# core.net
KiCad netlist of a schematic drawn in Altium Designer
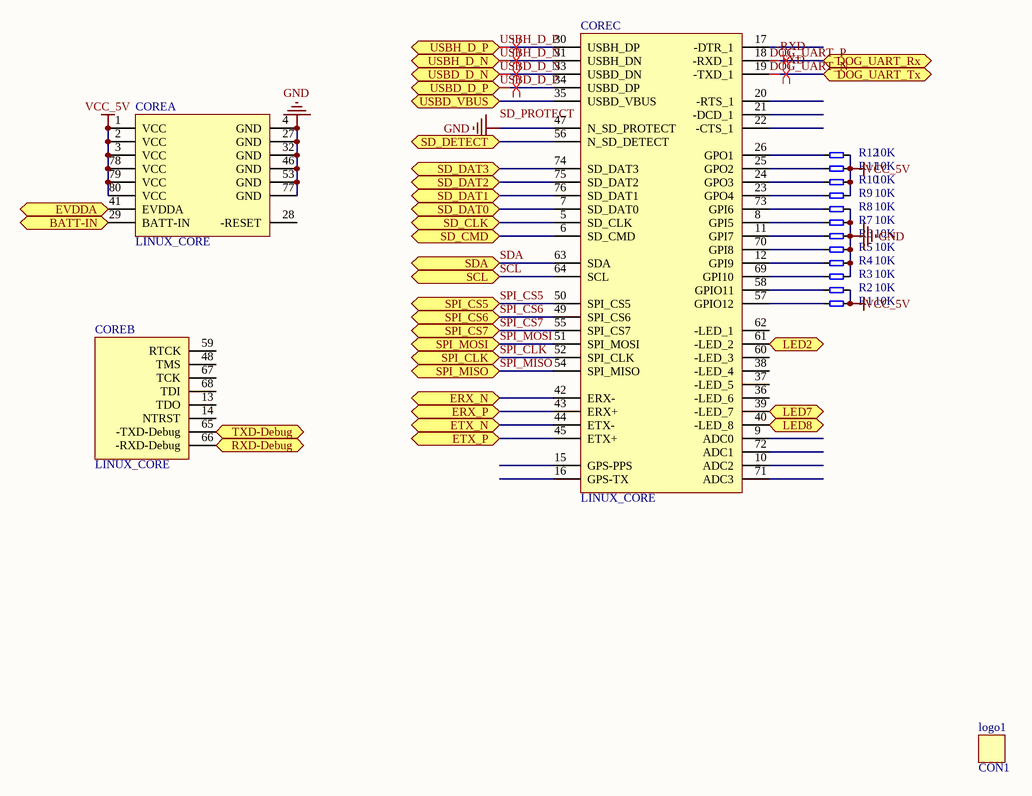
[diagram p0: core.SchDoc]

(export (version "E")
  (design (tool "Eeschema 10.0.6"))
  (components
    (comp (ref "CORE")
      (value "LINUX_CORE")
      (footprint "LINUX_CORE")
      (libsource (lib "Schlib1") (part "LINUX_CORE"))
    )
    (comp (ref "logo1")
      (value "CON1")
      (footprint "logo")
      (description "Connector")
      (libsource (lib "接插件") (part "CON1"))
    )
    (comp (ref "R1")
      (value "10K")
      (footprint "0805/2012 R3")
      (description "Resistor")
      (libsource (lib "标准元件库") (part "RES2"))
    )
    (comp (ref "R2")
      (value "10K")
      (footprint "0805/2012 R3")
      (description "Resistor")
      (libsource (lib "标准元件库") (part "RES2"))
    )
    (comp (ref "R3")
      (value "10K")
      (footprint "0805/2012 R3")
      (description "Resistor")
      (libsource (lib "标准元件库") (part "RES2"))
    )
    (comp (ref "R4")
      (value "10K")
      (footprint "0805/2012 R3")
      (description "Resistor")
      (libsource (lib "标准元件库") (part "RES2"))
    )
    (comp (ref "R5")
      (value "10K")
      (footprint "0805/2012 R3")
      (description "Resistor")
      (libsource (lib "标准元件库") (part "RES2"))
    )
    (comp (ref "R6")
      (value "10K")
      (footprint "0805/2012 R3")
      (description "Resistor")
      (libsource (lib "标准元件库") (part "RES2"))
    )
    (comp (ref "R7")
      (value "10K")
      (footprint "0805/2012 R3")
      (description "Resistor")
      (libsource (lib "标准元件库") (part "RES2"))
    )
    (comp (ref "R8")
      (value "10K")
      (footprint "0805/2012 R3")
      (description "Resistor")
      (libsource (lib "标准元件库") (part "RES2"))
    )
    (comp (ref "R9")
      (value "10K")
      (footprint "0805/2012 R3")
      (description "Resistor")
      (libsource (lib "标准元件库") (part "RES2"))
    )
    (comp (ref "R10")
      (value "10K")
      (footprint "0805/2012 R3")
      (description "Resistor")
      (libsource (lib "标准元件库") (part "RES2"))
    )
    (comp (ref "R11")
      (value "10K")
      (footprint "0805/2012 R3")
      (description "Resistor")
      (libsource (lib "标准元件库") (part "RES2"))
    )
    (comp (ref "R12")
      (value "10K")
      (footprint "0805/2012 R3")
      (description "Resistor")
      (libsource (lib "标准元件库") (part "RES2"))
    )
  )
  (nets
    (net (code "3") (name "/BATT-IN") (class "Default")
      (node (ref "CORE") (pin "29") (pinfunction "BATT-IN_29") (pintype "passive"))
    )
    (net (code "4") (name "/DOG_UART_N") (class "Default")
      (node (ref "CORE") (pin "19") (pinfunction "-TXD_1_19") (pintype "passive"))
    )
    (net (code "5") (name "/DOG_UART_P") (class "Default")
      (node (ref "CORE") (pin "18") (pinfunction "-RXD_1_18") (pintype "passive"))
    )
    (net (code "6") (name "/ERX_N") (class "Default")
      (node (ref "CORE") (pin "42") (pinfunction "ERX-_42") (pintype "passive"))
    )
    (net (code "7") (name "/ERX_P") (class "Default")
      (node (ref "CORE") (pin "43") (pinfunction "ERX+_43") (pintype "passive"))
    )
    (net (code "8") (name "/ETX_N") (class "Default")
      (node (ref "CORE") (pin "44") (pinfunction "ETX-_44") (pintype "passive"))
    )
    (net (code "9") (name "/ETX_P") (class "Default")
      (node (ref "CORE") (pin "45") (pinfunction "ETX+_45") (pintype "passive"))
    )
    (net (code "10") (name "/EVDDA") (class "Default")
      (node (ref "CORE") (pin "41") (pinfunction "EVDDA_41") (pintype "passive"))
    )
    (net (code "11") (name "/LED2") (class "Default")
      (node (ref "CORE") (pin "61") (pinfunction "-LED_2_61") (pintype "passive"))
    )
    (net (code "12") (name "/LED7") (class "Default")
      (node (ref "CORE") (pin "39") (pinfunction "-LED_7_39") (pintype "passive"))
    )
    (net (code "13") (name "/LED8") (class "Default")
      (node (ref "CORE") (pin "40") (pinfunction "-LED_8_40") (pintype "passive"))
    )
    (net (code "14") (name "/RXD-Debug") (class "Default")
      (node (ref "CORE") (pin "66") (pinfunction "-RXD-Debug_66") (pintype "passive"))
    )
    (net (code "15") (name "/SCL") (class "Default")
      (node (ref "CORE") (pin "64") (pinfunction "SCL_64") (pintype "passive"))
    )
    (net (code "16") (name "/SDA") (class "Default")
      (node (ref "CORE") (pin "63") (pinfunction "SDA_63") (pintype "passive"))
    )
    (net (code "17") (name "/SD_CLK") (class "Default")
      (node (ref "CORE") (pin "5") (pinfunction "SD_CLK_5") (pintype "passive"))
    )
    (net (code "18") (name "/SD_CMD") (class "Default")
      (node (ref "CORE") (pin "6") (pinfunction "SD_CMD_6") (pintype "passive"))
    )
    (net (code "19") (name "/SD_DAT0") (class "Default")
      (node (ref "CORE") (pin "7") (pinfunction "SD_DAT0_7") (pintype "passive"))
    )
    (net (code "20") (name "/SD_DAT1") (class "Default")
      (node (ref "CORE") (pin "76") (pinfunction "SD_DAT1_76") (pintype "passive"))
    )
    (net (code "21") (name "/SD_DAT2") (class "Default")
      (node (ref "CORE") (pin "75") (pinfunction "SD_DAT2_75") (pintype "passive"))
    )
    (net (code "22") (name "/SD_DAT3") (class "Default")
      (node (ref "CORE") (pin "74") (pinfunction "SD_DAT3_74") (pintype "passive"))
    )
    (net (code "23") (name "/SD_DETECT") (class "Default")
      (node (ref "CORE") (pin "56") (pinfunction "N_SD_DETECT_56") (pintype "passive"))
    )
    (net (code "25") (name "/SPI_CLK") (class "Default")
      (node (ref "CORE") (pin "52") (pinfunction "SPI_CLK_52") (pintype "passive"))
    )
    (net (code "26") (name "/SPI_CS5") (class "Default")
      (node (ref "CORE") (pin "50") (pinfunction "SPI_CS5_50") (pintype "passive"))
    )
    (net (code "27") (name "/SPI_CS6") (class "Default")
      (node (ref "CORE") (pin "49") (pinfunction "SPI_CS6_49") (pintype "passive"))
    )
    (net (code "28") (name "/SPI_CS7") (class "Default")
      (node (ref "CORE") (pin "55") (pinfunction "SPI_CS7_55") (pintype "passive"))
    )
    (net (code "29") (name "/SPI_MISO") (class "Default")
      (node (ref "CORE") (pin "54") (pinfunction "SPI_MISO_54") (pintype "passive"))
    )
    (net (code "30") (name "/SPI_MOSI") (class "Default")
      (node (ref "CORE") (pin "51") (pinfunction "SPI_MOSI_51") (pintype "passive"))
    )
    (net (code "31") (name "/TXD-Debug") (class "Default")
      (node (ref "CORE") (pin "65") (pinfunction "-TXD-Debug_65") (pintype "passive"))
    )
    (net (code "32") (name "/USBD_D_N") (class "Default")
      (node (ref "CORE") (pin "33") (pinfunction "USBD_DN_33") (pintype "passive"))
    )
    (net (code "33") (name "/USBD_D_P") (class "Default")
      (node (ref "CORE") (pin "34") (pinfunction "USBD_DP_34") (pintype "passive"))
    )
    (net (code "34") (name "/USBD_VBUS") (class "Default")
      (node (ref "CORE") (pin "35") (pinfunction "USBD_VBUS_35") (pintype "passive"))
    )
    (net (code "35") (name "/USBH_D_N") (class "Default")
      (node (ref "CORE") (pin "31") (pinfunction "USBH_DN_31") (pintype "passive"))
    )
    (net (code "36") (name "/USBH_D_P") (class "Default")
      (node (ref "CORE") (pin "30") (pinfunction "USBH_DP_30") (pintype "passive"))
    )
    (net (code "37") (name "GND") (class "Default")
      (node (ref "CORE") (pin "27") (pinfunction "GND_27") (pintype "passive"))
      (node (ref "CORE") (pin "32") (pinfunction "GND_32") (pintype "passive"))
      (node (ref "CORE") (pin "4") (pinfunction "GND_4") (pintype "passive"))
      (node (ref "CORE") (pin "46") (pinfunction "GND_46") (pintype "passive"))
      (node (ref "CORE") (pin "47") (pinfunction "N_SD_PROTECT_47") (pintype "passive"))
      (node (ref "CORE") (pin "53") (pinfunction "GND_53") (pintype "passive"))
      (node (ref "CORE") (pin "77") (pinfunction "GND_77") (pintype "passive"))
      (node (ref "R3") (pin "2") (pinfunction "2_2") (pintype "passive"))
      (node (ref "R4") (pin "2") (pinfunction "2_2") (pintype "passive"))
      (node (ref "R5") (pin "2") (pinfunction "2_2") (pintype "passive"))
      (node (ref "R6") (pin "2") (pinfunction "2_2") (pintype "passive"))
      (node (ref "R7") (pin "2") (pinfunction "2_2") (pintype "passive"))
      (node (ref "R8") (pin "2") (pinfunction "2_2") (pintype "passive"))
    )
    (net (code "38") (name "Net-(COREC-GPI5)") (class "Default")
      (node (ref "CORE") (pin "8") (pinfunction "GPI5_8") (pintype "passive"))
      (node (ref "R7") (pin "1") (pinfunction "1_1") (pintype "passive"))
    )
    (net (code "39") (name "Net-(COREC-GPI6)") (class "Default")
      (node (ref "CORE") (pin "73") (pinfunction "GPI6_73") (pintype "passive"))
      (node (ref "R8") (pin "1") (pinfunction "1_1") (pintype "passive"))
    )
    (net (code "40") (name "Net-(COREC-GPI7)") (class "Default")
      (node (ref "CORE") (pin "11") (pinfunction "GPI7_11") (pintype "passive"))
      (node (ref "R6") (pin "1") (pinfunction "1_1") (pintype "passive"))
    )
    (net (code "41") (name "Net-(COREC-GPI8)") (class "Default")
      (node (ref "CORE") (pin "70") (pinfunction "GPI8_70") (pintype "passive"))
      (node (ref "R5") (pin "1") (pinfunction "1_1") (pintype "passive"))
    )
    (net (code "42") (name "Net-(COREC-GPI9)") (class "Default")
      (node (ref "CORE") (pin "12") (pinfunction "GPI9_12") (pintype "passive"))
      (node (ref "R4") (pin "1") (pinfunction "1_1") (pintype "passive"))
    )
    (net (code "43") (name "Net-(COREC-GPI10)") (class "Default")
      (node (ref "CORE") (pin "69") (pinfunction "GPI10_69") (pintype "passive"))
      (node (ref "R3") (pin "1") (pinfunction "1_1") (pintype "passive"))
    )
    (net (code "44") (name "Net-(COREC-GPIO11)") (class "Default")
      (node (ref "CORE") (pin "58") (pinfunction "GPIO11_58") (pintype "passive"))
      (node (ref "R2") (pin "1") (pinfunction "1_1") (pintype "passive"))
    )
    (net (code "45") (name "Net-(COREC-GPIO12)") (class "Default")
      (node (ref "CORE") (pin "57") (pinfunction "GPIO12_57") (pintype "passive"))
      (node (ref "R1") (pin "1") (pinfunction "1_1") (pintype "passive"))
    )
    (net (code "46") (name "Net-(COREC-GPO1)") (class "Default")
      (node (ref "CORE") (pin "26") (pinfunction "GPO1_26") (pintype "passive"))
      (node (ref "R12") (pin "1") (pinfunction "1_1") (pintype "passive"))
    )
    (net (code "47") (name "Net-(COREC-GPO2)") (class "Default")
      (node (ref "CORE") (pin "25") (pinfunction "GPO2_25") (pintype "passive"))
      (node (ref "R11") (pin "1") (pinfunction "1_1") (pintype "passive"))
    )
    (net (code "48") (name "Net-(COREC-GPO3)") (class "Default")
      (node (ref "CORE") (pin "24") (pinfunction "GPO3_24") (pintype "passive"))
      (node (ref "R10") (pin "1") (pinfunction "1_1") (pintype "passive"))
    )
    (net (code "49") (name "Net-(COREC-GPO4)") (class "Default")
      (node (ref "CORE") (pin "23") (pinfunction "GPO4_23") (pintype "passive"))
      (node (ref "R9") (pin "1") (pinfunction "1_1") (pintype "passive"))
    )
    (net (code "50") (name "VCC_5V") (class "Default")
      (node (ref "CORE") (pin "1") (pinfunction "VCC_1") (pintype "passive"))
      (node (ref "CORE") (pin "2") (pinfunction "VCC_2") (pintype "passive"))
      (node (ref "CORE") (pin "3") (pinfunction "VCC_3") (pintype "passive"))
      (node (ref "CORE") (pin "78") (pinfunction "VCC_78") (pintype "passive"))
      (node (ref "CORE") (pin "79") (pinfunction "VCC_79") (pintype "passive"))
      (node (ref "CORE") (pin "80") (pinfunction "VCC_80") (pintype "passive"))
      (node (ref "R1") (pin "2") (pinfunction "2_2") (pintype "passive"))
      (node (ref "R10") (pin "2") (pinfunction "2_2") (pintype "passive"))
      (node (ref "R11") (pin "2") (pinfunction "2_2") (pintype "passive"))
      (node (ref "R12") (pin "2") (pinfunction "2_2") (pintype "passive"))
      (node (ref "R2") (pin "2") (pinfunction "2_2") (pintype "passive"))
      (node (ref "R9") (pin "2") (pinfunction "2_2") (pintype "passive"))
    )
    (net (code "51") (name "unconnected-(COREA--RESET-Pad28)") (class "Default")
      (node (ref "CORE") (pin "28") (pinfunction "-RESET_28") (pintype "passive"))
    )
    (net (code "52") (name "unconnected-(COREB-NTRST-Pad14)") (class "Default")
      (node (ref "CORE") (pin "14") (pinfunction "NTRST_14") (pintype "passive"))
    )
    (net (code "53") (name "unconnected-(COREB-RTCK-Pad59)") (class "Default")
      (node (ref "CORE") (pin "59") (pinfunction "RTCK_59") (pintype "passive"))
    )
    (net (code "54") (name "unconnected-(COREB-TCK-Pad67)") (class "Default")
      (node (ref "CORE") (pin "67") (pinfunction "TCK_67") (pintype "passive"))
    )
    (net (code "55") (name "unconnected-(COREB-TDI-Pad68)") (class "Default")
      (node (ref "CORE") (pin "68") (pinfunction "TDI_68") (pintype "passive"))
    )
    (net (code "56") (name "unconnected-(COREB-TDO-Pad13)") (class "Default")
      (node (ref "CORE") (pin "13") (pinfunction "TDO_13") (pintype "passive"))
    )
    (net (code "57") (name "unconnected-(COREB-TMS-Pad48)") (class "Default")
      (node (ref "CORE") (pin "48") (pinfunction "TMS_48") (pintype "passive"))
    )
    (net (code "58") (name "unconnected-(COREC--CTS_1-Pad22)") (class "Default")
      (node (ref "CORE") (pin "22") (pinfunction "-CTS_1_22") (pintype "passive"))
    )
    (net (code "59") (name "unconnected-(COREC--DCD_1-Pad21)") (class "Default")
      (node (ref "CORE") (pin "21") (pinfunction "-DCD_1_21") (pintype "passive"))
    )
    (net (code "60") (name "unconnected-(COREC--DTR_1-Pad17)") (class "Default")
      (node (ref "CORE") (pin "17") (pinfunction "-DTR_1_17") (pintype "passive"))
    )
    (net (code "61") (name "unconnected-(COREC--LED_1-Pad62)") (class "Default")
      (node (ref "CORE") (pin "62") (pinfunction "-LED_1_62") (pintype "passive"))
    )
    (net (code "62") (name "unconnected-(COREC--LED_3-Pad60)") (class "Default")
      (node (ref "CORE") (pin "60") (pinfunction "-LED_3_60") (pintype "passive"))
    )
    (net (code "63") (name "unconnected-(COREC--LED_4-Pad38)") (class "Default")
      (node (ref "CORE") (pin "38") (pinfunction "-LED_4_38") (pintype "passive"))
    )
    (net (code "64") (name "unconnected-(COREC--LED_5-Pad37)") (class "Default")
      (node (ref "CORE") (pin "37") (pinfunction "-LED_5_37") (pintype "passive"))
    )
    (net (code "65") (name "unconnected-(COREC--LED_6-Pad36)") (class "Default")
      (node (ref "CORE") (pin "36") (pinfunction "-LED_6_36") (pintype "passive"))
    )
    (net (code "66") (name "unconnected-(COREC--RTS_1-Pad20)") (class "Default")
      (node (ref "CORE") (pin "20") (pinfunction "-RTS_1_20") (pintype "passive"))
    )
    (net (code "67") (name "unconnected-(COREC-ADC0-Pad9)") (class "Default")
      (node (ref "CORE") (pin "9") (pinfunction "ADC0_9") (pintype "passive"))
    )
    (net (code "68") (name "unconnected-(COREC-ADC1-Pad72)") (class "Default")
      (node (ref "CORE") (pin "72") (pinfunction "ADC1_72") (pintype "passive"))
    )
    (net (code "69") (name "unconnected-(COREC-ADC2-Pad10)") (class "Default")
      (node (ref "CORE") (pin "10") (pinfunction "ADC2_10") (pintype "passive"))
    )
    (net (code "70") (name "unconnected-(COREC-ADC3-Pad71)") (class "Default")
      (node (ref "CORE") (pin "71") (pinfunction "ADC3_71") (pintype "passive"))
    )
    (net (code "71") (name "unconnected-(COREC-GPS-PPS-Pad15)") (class "Default")
      (node (ref "CORE") (pin "15") (pinfunction "GPS-PPS_15") (pintype "passive"))
    )
    (net (code "72") (name "unconnected-(COREC-GPS-TX-Pad16)") (class "Default")
      (node (ref "CORE") (pin "16") (pinfunction "GPS-TX_16") (pintype "passive"))
    )
    (net (code "73") (name "unconnected-(logo1-Pad1)") (class "Default")
      (node (ref "logo1") (pin "1") (pinfunction "1_1") (pintype "passive"))
    )
  )
)
